# Page08_CPU_MISC.net
KiCad netlist of a schematic drawn in Altium Designer
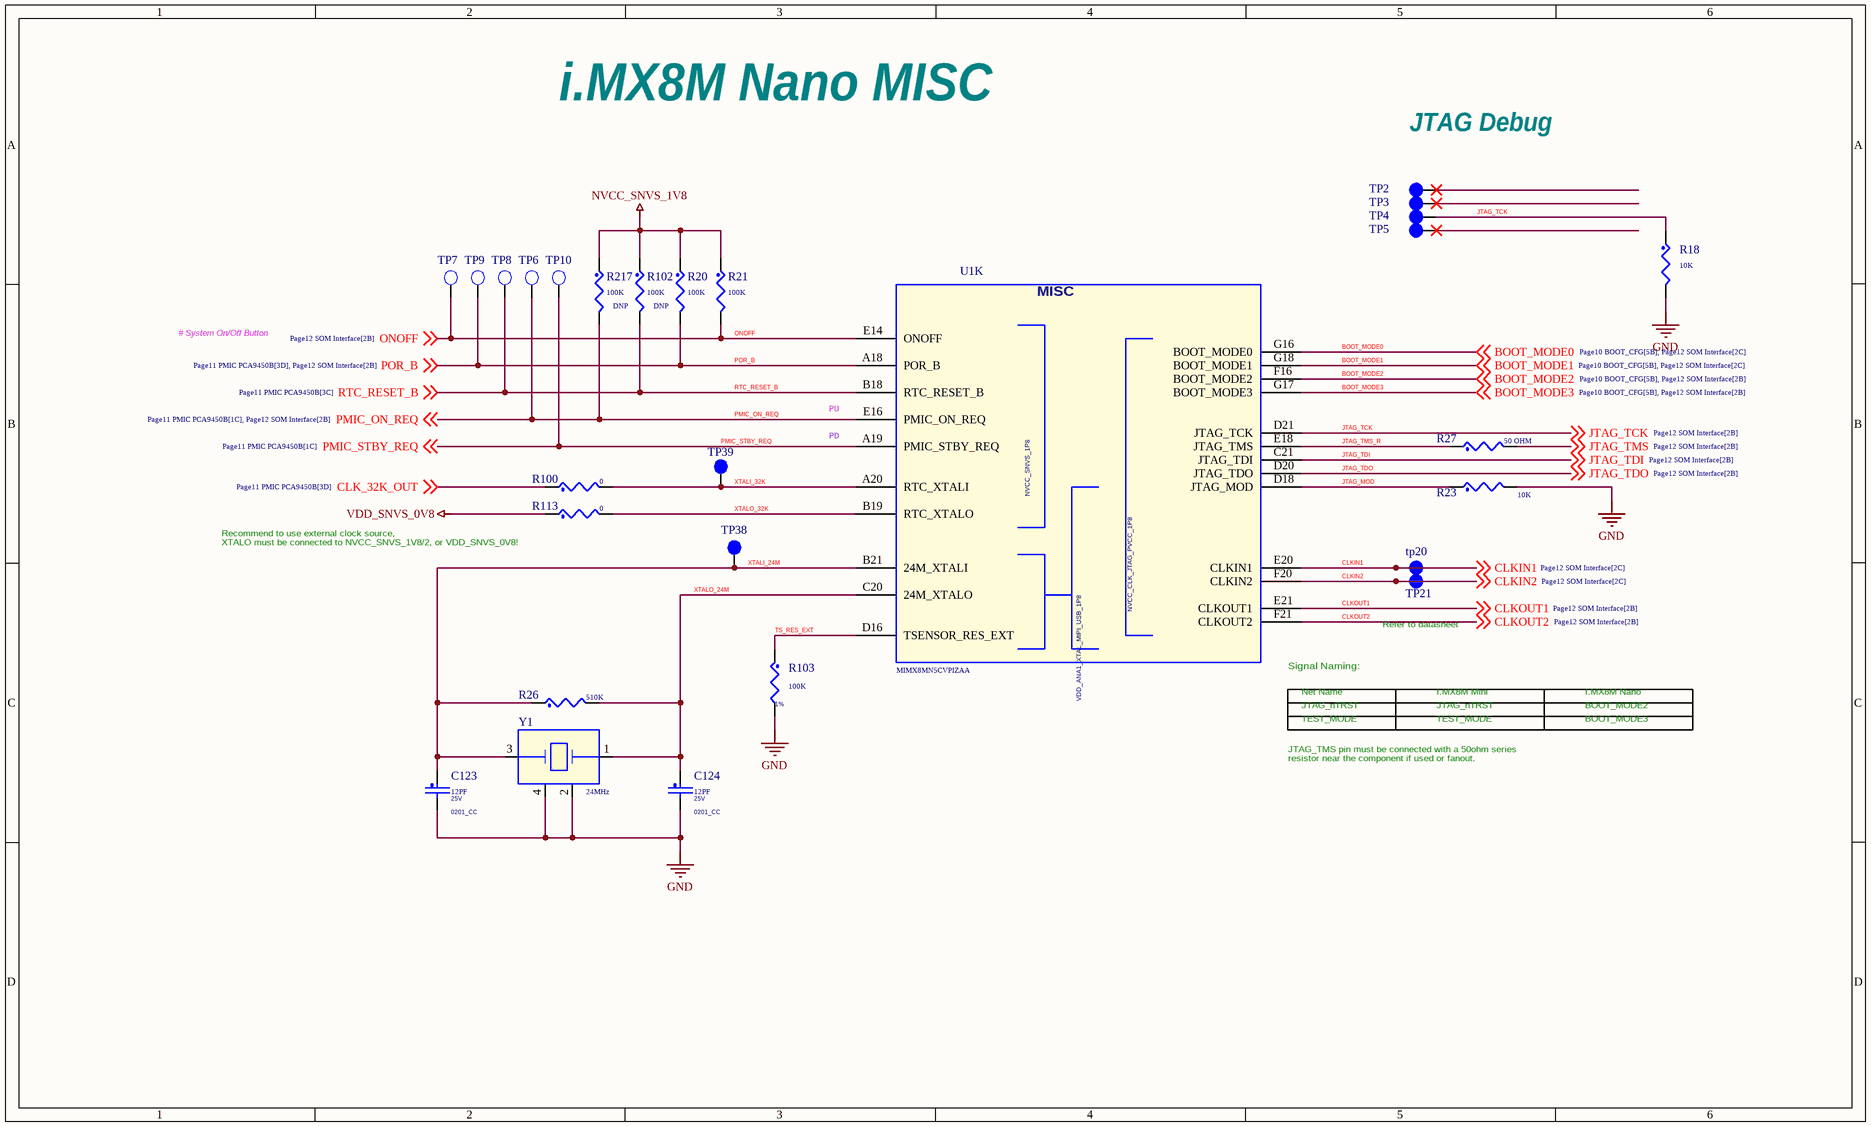
[diagram p0: Page08 CPU MISC.SchDoc]

(export (version "E")
  (design (tool "Eeschema 10.0.6"))
  (components
    (comp (ref "C123")
      (value "12PF")
      (footprint "0201_CC - C")
      (description "CAP CER 12PF 25V 5% C0G AEC-Q200 0201")
      (fields
        (field (name "VOLTAGE") "25V")
        (field (name "TOLERANCE") "5%")
        (field (name "PCB FOOTPRINT") "0201_CC")
      )
      (libsource (lib "*") (part "CAP_NP"))
    )
    (comp (ref "C124")
      (value "12PF")
      (footprint "0201_CC - C")
      (description "CAP CER 12PF 25V 5% C0G AEC-Q200 0201")
      (fields
        (field (name "TOLERANCE") "5%")
        (field (name "VOLTAGE") "25V")
        (field (name "PCB FOOTPRINT") "0201_CC")
      )
      (libsource (lib "*") (part "CAP_NP"))
    )
    (comp (ref "R18")
      (value "10K")
      (footprint "0201_RES")
      (description "RES MF 10K 1/20W 5% 0201")
      (fields (field (name "TOLERANCE") "5%"))
      (libsource (lib "*") (part "RES"))
    )
    (comp (ref "R20")
      (value "100K")
      (footprint "0201_RES")
      (description "RES MF 100K 1/20W 1% 0201")
      (fields (field (name "TOLERANCE") "1%"))
      (libsource (lib "*") (part "RES"))
    )
    (comp (ref "R21")
      (value "100K")
      (footprint "0201_RES")
      (description "RES MF 100K 1/20W 1% 0201")
      (fields (field (name "TOLERANCE") "1%"))
      (libsource (lib "*") (part "RES"))
    )
    (comp (ref "R23")
      (value "10K")
      (footprint "0201_RES")
      (description "RES MF 10K 1/20W 5% 0201")
      (fields (field (name "TOLERANCE") "5%"))
      (libsource (lib "*") (part "RES"))
    )
    (comp (ref "R26")
      (value "510K")
      (footprint "0402_CC_RES")
      (description "RES MF 510K 1/16W 5% 0402")
      (fields (field (name "TOLERANCE") "5%"))
      (libsource (lib "*") (part "RES"))
    )
    (comp (ref "R27")
      (value "50 OHM")
      (footprint "0402_CC_RES")
      (description "RES MF 50 OHM 1/20W 5% 0402")
      (fields (field (name "TOLERANCE") "5%"))
      (libsource (lib "*") (part "RES"))
    )
    (comp (ref "R100")
      (value "0")
      (footprint "0402_CC_RES")
      (description "RES MF ZERO OHM 1/16W 5% 0402")
      (fields (field (name "TOLERANCE") "5%") (field (name "VOLTAGE") "1/16W"))
      (libsource (lib "*") (part "RES"))
    )
    (comp (ref "R102")
      (value "100K")
      (footprint "0201_RES")
      (description "RES MF 100K 1/20W 1% 0201")
      (fields (field (name "ASSY_OPT") "DNP") (field (name "TOLERANCE") "1%"))
      (libsource (lib "*") (part "RES"))
    )
    (comp (ref "R103")
      (value "100K")
      (footprint "0201_RES")
      (description "RES MF 100K 1/20W 1% 0201")
      (fields (field (name "TOLERANCE") "1%"))
      (libsource (lib "*") (part "RES"))
    )
    (comp (ref "R113")
      (value "0")
      (footprint "0402_CC_RES")
      (description "RES MF ZERO OHM 1/16W 5% 0402")
      (fields (field (name "TOLERANCE") "5%") (field (name "VOLTAGE") "1/16W"))
      (libsource (lib "*") (part "RES"))
    )
    (comp (ref "R217")
      (value "100K")
      (footprint "0201_RES")
      (description "RES MF 100K 1/20W 1% 0201")
      (fields (field (name "ASSY_OPT") "DNP") (field (name "TOLERANCE") "1%"))
      (libsource (lib "*") (part "RES"))
    )
    (comp (ref "TP2")
      (value "tpad_020")
      (footprint "Test Pin")
      (description "TEST POINT PAD 0.5MM DIA SMT, NO PART TO ORDER")
      (libsource (lib "*") (part "TESTLOOP"))
    )
    (comp (ref "TP3")
      (value "tpad_020")
      (footprint "Test Pin")
      (description "TEST POINT PAD 0.5MM DIA SMT, NO PART TO ORDER")
      (libsource (lib "*") (part "TESTLOOP"))
    )
    (comp (ref "TP4")
      (value "tpad_020")
      (footprint "Test Pin")
      (description "TEST POINT PAD 0.5MM DIA SMT, NO PART TO ORDER")
      (libsource (lib "*") (part "TESTLOOP"))
    )
    (comp (ref "TP5")
      (value "tpad_020")
      (footprint "Test Pin")
      (description "TEST POINT PAD 0.5MM DIA SMT, NO PART TO ORDER")
      (libsource (lib "*") (part "TESTLOOP"))
    )
    (comp (ref "TP6")
      (value "TP_35MIL")
      (footprint "Test Pin")
      (description "TEST POINT PAD .035 SMT, no part to order")
      (libsource (lib "*") (part "T POINT R"))
    )
    (comp (ref "TP7")
      (value "TP_35MIL")
      (footprint "Test Pin")
      (description "TEST POINT PAD .035 SMT, no part to order")
      (libsource (lib "*") (part "T POINT R"))
    )
    (comp (ref "TP8")
      (value "TP_35MIL")
      (footprint "Test Pin")
      (description "TEST POINT PAD .035 SMT, no part to order")
      (libsource (lib "*") (part "T POINT R"))
    )
    (comp (ref "TP9")
      (value "TP_35MIL")
      (footprint "Test Pin")
      (description "TEST POINT PAD .035 SMT, no part to order")
      (libsource (lib "*") (part "T POINT R"))
    )
    (comp (ref "TP10")
      (value "TP_35MIL")
      (footprint "Test Pin")
      (description "TEST POINT PAD .035 SMT, no part to order")
      (libsource (lib "*") (part "T POINT R"))
    )
    (comp (ref "tp20")
      (value "tpad_020")
      (footprint "Test Pin")
      (description "TEST POINT PAD 0.5MM DIA SMT, NO PART TO ORDER")
      (libsource (lib "*") (part "TESTLOOP"))
    )
    (comp (ref "TP21")
      (value "tpad_020")
      (footprint "Test Pin")
      (description "TEST POINT PAD 0.5MM DIA SMT, NO PART TO ORDER")
      (libsource (lib "*") (part "TESTLOOP"))
    )
    (comp (ref "TP38")
      (value "tpad_020")
      (footprint "Test Pin")
      (description "TEST POINT PAD 0.5MM DIA SMT, NO PART TO ORDER")
      (libsource (lib "*") (part "TESTLOOP"))
    )
    (comp (ref "TP39")
      (value "tpad_020")
      (footprint "Test Pin")
      (description "TEST POINT PAD 0.5MM DIA SMT, NO PART TO ORDER")
      (libsource (lib "*") (part "TESTLOOP"))
    )
    (comp (ref "U1")
      (value "MIMX8MN5CVPIZAA")
      (footprint "BGA306C50P21X21_1100X1100X101")
      (description "IC CPU QUAD CORTEX A53+M7 1.4GHZ -- BGA306")
      (libsource (lib "*") (part "MIMX8MN"))
    )
    (comp (ref "Y1")
      (value "24MHz")
      (footprint "OSCCC320X250X60")
      (description "XTAL 24MHZ 9pF -- SMT 3.2X2.5MM")
      (libsource (lib "*") (part "XTAL_13"))
    )
  )
  (nets
    (net (code "1") (name "/JTAG_MOD") (class "Default")
      (node (ref "R23") (pin "1") (pinfunction "1_1") (pintype "passive"))
      (node (ref "U1") (pin "D18") (pinfunction "JTAG_MOD_D18") (pintype "passive"))
    )
    (net (code "2") (name "/JTAG_TMS_R") (class "Default")
      (node (ref "R27") (pin "1") (pinfunction "1_1") (pintype "passive"))
      (node (ref "U1") (pin "E18") (pinfunction "JTAG_TMS_E18") (pintype "passive"))
    )
    (net (code "3") (name "/TS_RES_EXT") (class "Default")
      (node (ref "R103") (pin "1") (pinfunction "1_1") (pintype "passive"))
      (node (ref "U1") (pin "D16") (pinfunction "TSENSOR_RES_EXT_D16") (pintype "passive"))
    )
    (net (code "4") (name "/XTALI_24M") (class "Default")
      (node (ref "C123") (pin "1") (pinfunction "1_1") (pintype "passive"))
      (node (ref "R26") (pin "1") (pinfunction "1_1") (pintype "passive"))
      (node (ref "TP38") (pin "1") (pinfunction "Pin1_1") (pintype "passive"))
      (node (ref "U1") (pin "B21") (pinfunction "24M_XTALI_B21") (pintype "passive"))
      (node (ref "Y1") (pin "3") (pinfunction "3_3") (pintype "passive"))
    )
    (net (code "5") (name "/XTALI_32K") (class "Default")
      (node (ref "R100") (pin "2") (pinfunction "2_2") (pintype "passive"))
      (node (ref "TP39") (pin "1") (pinfunction "Pin1_1") (pintype "passive"))
      (node (ref "U1") (pin "A20") (pinfunction "RTC_XTALI_A20") (pintype "passive"))
    )
    (net (code "6") (name "/XTALO_24M") (class "Default")
      (node (ref "C124") (pin "1") (pinfunction "1_1") (pintype "passive"))
      (node (ref "R26") (pin "2") (pinfunction "2_2") (pintype "passive"))
      (node (ref "U1") (pin "C20") (pinfunction "24M_XTALO_C20") (pintype "passive"))
      (node (ref "Y1") (pin "1") (pinfunction "1_1") (pintype "passive"))
    )
    (net (code "7") (name "/XTALO_32K") (class "Default")
      (node (ref "R113") (pin "2") (pinfunction "2_2") (pintype "passive"))
      (node (ref "U1") (pin "B19") (pinfunction "RTC_XTALO_B19") (pintype "passive"))
    )
    (net (code "8") (name "BOOT_MODE0") (class "Default")
      (node (ref "U1") (pin "G16") (pinfunction "BOOT_MODE0_G16") (pintype "passive"))
    )
    (net (code "9") (name "BOOT_MODE1") (class "Default")
      (node (ref "U1") (pin "G18") (pinfunction "BOOT_MODE1_G18") (pintype "passive"))
    )
    (net (code "10") (name "BOOT_MODE2") (class "Default")
      (node (ref "U1") (pin "F16") (pinfunction "BOOT_MODE2_F16") (pintype "passive"))
    )
    (net (code "11") (name "BOOT_MODE3") (class "Default")
      (node (ref "U1") (pin "G17") (pinfunction "BOOT_MODE3_G17") (pintype "passive"))
    )
    (net (code "12") (name "CLKIN1") (class "Default")
      (node (ref "U1") (pin "E20") (pinfunction "CLKIN1_E20") (pintype "passive"))
      (node (ref "tp20") (pin "1") (pinfunction "Pin1_1") (pintype "passive"))
    )
    (net (code "13") (name "CLKIN2") (class "Default")
      (node (ref "TP21") (pin "1") (pinfunction "Pin1_1") (pintype "passive"))
      (node (ref "U1") (pin "F20") (pinfunction "CLKIN2_F20") (pintype "passive"))
    )
    (net (code "14") (name "CLKOUT1") (class "Default")
      (node (ref "U1") (pin "E21") (pinfunction "CLKOUT1_E21") (pintype "passive"))
    )
    (net (code "15") (name "CLKOUT2") (class "Default")
      (node (ref "U1") (pin "F21") (pinfunction "CLKOUT2_F21") (pintype "passive"))
    )
    (net (code "16") (name "CLK_32K_OUT") (class "Default")
      (node (ref "R100") (pin "1") (pinfunction "1_1") (pintype "passive"))
    )
    (net (code "17") (name "GND") (class "Default")
      (node (ref "C123") (pin "2") (pinfunction "2_2") (pintype "passive"))
      (node (ref "C124") (pin "2") (pinfunction "2_2") (pintype "passive"))
      (node (ref "R103") (pin "2") (pinfunction "2_2") (pintype "passive"))
      (node (ref "R18") (pin "2") (pinfunction "2_2") (pintype "passive"))
      (node (ref "R23") (pin "2") (pinfunction "2_2") (pintype "passive"))
      (node (ref "Y1") (pin "2") (pinfunction "2_2") (pintype "passive"))
      (node (ref "Y1") (pin "4") (pinfunction "4_4") (pintype "passive"))
    )
    (net (code "18") (name "JTAG_TCK") (class "Default")
      (node (ref "R18") (pin "1") (pinfunction "1_1") (pintype "passive"))
      (node (ref "TP4") (pin "1") (pinfunction "Pin1_1") (pintype "passive"))
      (node (ref "U1") (pin "D21") (pinfunction "JTAG_TCK_D21") (pintype "passive"))
    )
    (net (code "19") (name "JTAG_TDI") (class "Default")
      (node (ref "U1") (pin "C21") (pinfunction "JTAG_TDI_C21") (pintype "passive"))
    )
    (net (code "20") (name "JTAG_TDO") (class "Default")
      (node (ref "U1") (pin "D20") (pinfunction "JTAG_TDO_D20") (pintype "passive"))
    )
    (net (code "21") (name "JTAG_TMS") (class "Default")
      (node (ref "R27") (pin "2") (pinfunction "2_2") (pintype "passive"))
    )
    (net (code "22") (name "NVCC_SNVS_1V8") (class "Default")
      (node (ref "R102") (pin "1") (pinfunction "1_1") (pintype "passive"))
      (node (ref "R20") (pin "1") (pinfunction "1_1") (pintype "passive"))
      (node (ref "R21") (pin "1") (pinfunction "1_1") (pintype "passive"))
      (node (ref "R217") (pin "1") (pinfunction "1_1") (pintype "passive"))
    )
    (net (code "23") (name "ONOFF") (class "Default")
      (node (ref "R21") (pin "2") (pinfunction "2_2") (pintype "passive"))
      (node (ref "TP7") (pin "1") (pinfunction "TP_1") (pintype "passive"))
      (node (ref "U1") (pin "E14") (pinfunction "ONOFF_E14") (pintype "passive"))
    )
    (net (code "24") (name "PMIC_ON_REQ") (class "Default")
      (node (ref "R217") (pin "2") (pinfunction "2_2") (pintype "passive"))
      (node (ref "TP6") (pin "1") (pinfunction "TP_1") (pintype "passive"))
      (node (ref "U1") (pin "E16") (pinfunction "PMIC_ON_REQ_E16") (pintype "passive"))
    )
    (net (code "25") (name "PMIC_STBY_REQ") (class "Default")
      (node (ref "TP10") (pin "1") (pinfunction "TP_1") (pintype "passive"))
      (node (ref "U1") (pin "A19") (pinfunction "PMIC_STBY_REQ_A19") (pintype "passive"))
    )
    (net (code "26") (name "POR_B") (class "Default")
      (node (ref "R20") (pin "2") (pinfunction "2_2") (pintype "passive"))
      (node (ref "TP9") (pin "1") (pinfunction "TP_1") (pintype "passive"))
      (node (ref "U1") (pin "A18") (pinfunction "POR_B_A18") (pintype "passive"))
    )
    (net (code "27") (name "RTC_RESET_B") (class "Default")
      (node (ref "R102") (pin "2") (pinfunction "2_2") (pintype "passive"))
      (node (ref "TP8") (pin "1") (pinfunction "TP_1") (pintype "passive"))
      (node (ref "U1") (pin "B18") (pinfunction "RTC_RESET_B_B18") (pintype "passive"))
    )
    (net (code "28") (name "VDD_SNVS_0V8") (class "Default")
      (node (ref "R113") (pin "1") (pinfunction "1_1") (pintype "passive"))
    )
    (net (code "29") (name "unconnected-(TP2-Pin1-Pad1)") (class "Default")
      (node (ref "TP2") (pin "1") (pinfunction "Pin1_1") (pintype "passive+no_connect"))
    )
    (net (code "30") (name "unconnected-(TP3-Pin1-Pad1)") (class "Default")
      (node (ref "TP3") (pin "1") (pinfunction "Pin1_1") (pintype "passive+no_connect"))
    )
    (net (code "31") (name "unconnected-(TP5-Pin1-Pad1)") (class "Default")
      (node (ref "TP5") (pin "1") (pinfunction "Pin1_1") (pintype "passive+no_connect"))
    )
  )
)
